# Embedded_Circuits.net
KiCad netlist of a schematic drawn in Altium Designer
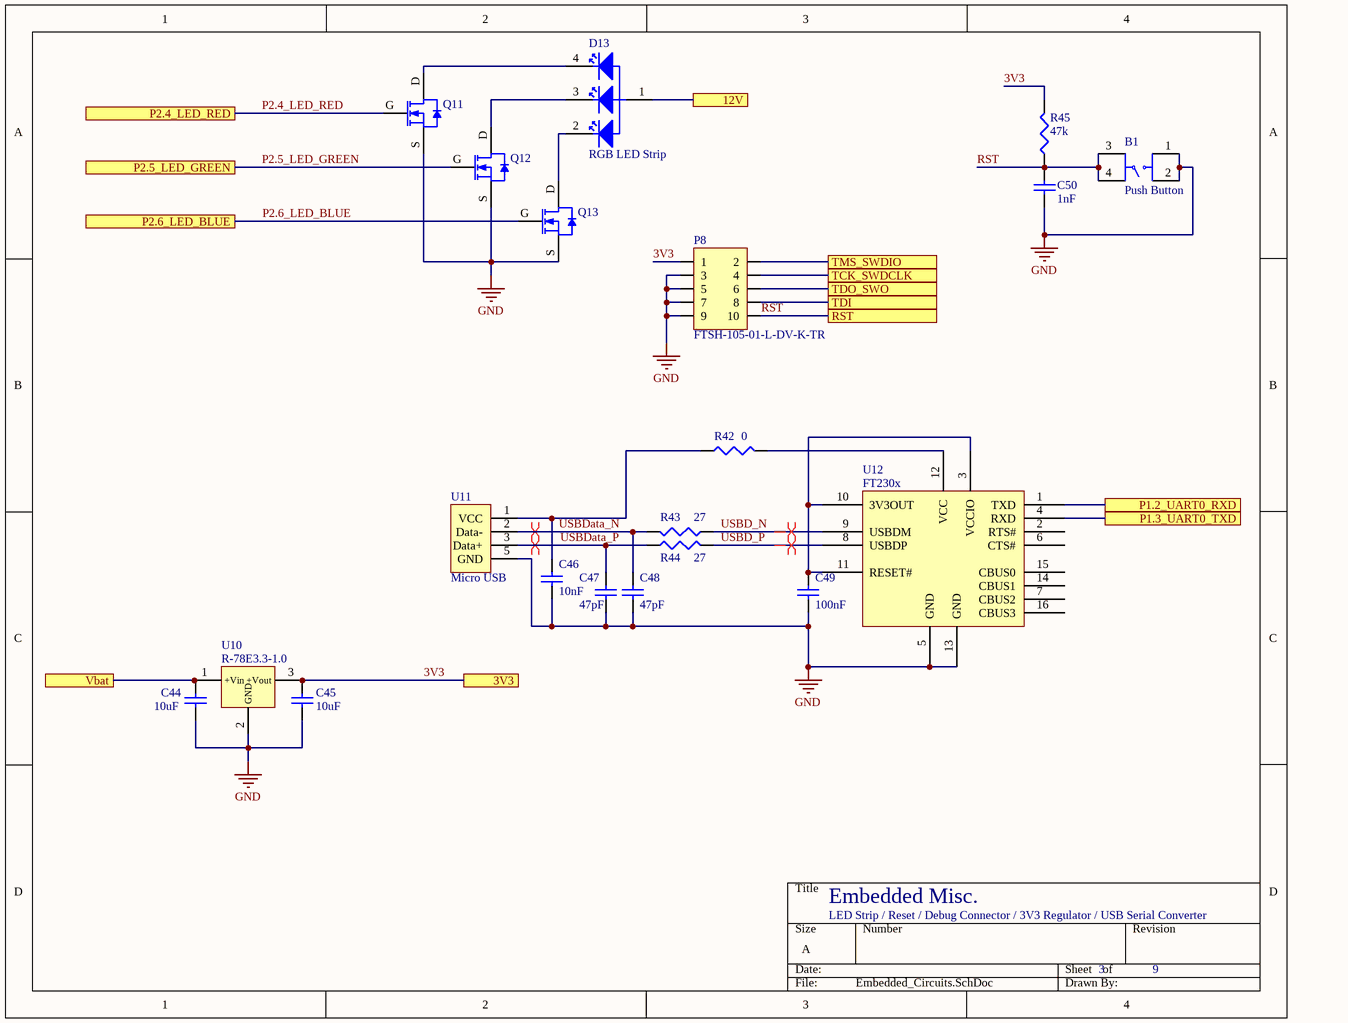
[diagram p0: Embedded_Circuits.SchDoc]

(export (version "E")
  (design (tool "Eeschema 10.0.6"))
  (components
    (comp (ref "B1")
      (value "Push Button")
      (footprint "Push Button")
      (description "Tactile Switch SPST-NO Top Actuated Through Hole")
      (libsource (lib "Power_Embedded_Board_Library") (part "Push Button"))
    )
    (comp (ref "C44")
      (value "10uF")
      (footprint "C1206")
      (description "Capacitor")
      (fields (field (name "Comment") "Cap") (field (name "PUBLISHER") "Altium Limited"))
      (libsource (lib "Miscellaneous Devices") (part "Cap"))
    )
    (comp (ref "C45")
      (value "10uF")
      (footprint "C1206")
      (description "Capacitor")
      (fields (field (name "Comment") "Cap") (field (name "PUBLISHER") "Altium Limited"))
      (libsource (lib "Miscellaneous Devices") (part "Cap"))
    )
    (comp (ref "C46")
      (value "10nF")
      (footprint "C1206")
      (description "Capacitor")
      (fields (field (name "Comment") "Cap") (field (name "PUBLISHER") "Altium Limited"))
      (libsource (lib "Miscellaneous Devices") (part "Cap"))
    )
    (comp (ref "C47")
      (value "47pF")
      (footprint "C1206")
      (description "Capacitor")
      (fields (field (name "Comment") "Cap") (field (name "PUBLISHER") "Altium Limited"))
      (libsource (lib "Miscellaneous Devices") (part "Cap"))
    )
    (comp (ref "C48")
      (value "47pF")
      (footprint "C1206")
      (description "Capacitor")
      (fields (field (name "Comment") "Cap") (field (name "PUBLISHER") "Altium Limited"))
      (libsource (lib "Miscellaneous Devices") (part "Cap"))
    )
    (comp (ref "C49")
      (value "100nF")
      (footprint "C1206")
      (description "Capacitor")
      (fields (field (name "Comment") "Cap") (field (name "PUBLISHER") "Altium Limited"))
      (libsource (lib "Miscellaneous Devices") (part "Cap"))
    )
    (comp (ref "C50")
      (value "1nF")
      (footprint "C1206")
      (description "Capacitor (Semiconductor SIM Model)")
      (fields (field (name "Comment") "Cap Semi") (field (name "PUBLISHER") "Altium Limited"))
      (libsource (lib "Miscellaneous Devices") (part "Cap Semi"))
    )
    (comp (ref "D13")
      (value "RGB LED Strip")
      (footprint "Header 1x4")
      (description "LED RGB Strip - Bare Nonaddressable")
      (libsource (lib "Power_Embedded_Board_Library") (part "RGB LED Strip"))
    )
    (comp (ref "P8")
      (value "FTSH-105-01-L-DV-K-TR")
      (footprint "FTSH-105-01-L-DV-K-TR")
      (description "CONN HEADER 10POS DUAL .05\" SMD")
      (libsource (lib "Power_Embedded_Board_Library") (part "JTAG Header"))
    )
    (comp (ref "Q11")
      (value "DMN1019USN")
      (footprint "DMN1019USN")
      (description "12V N-Channel Enhancement Mode MOSFET")
      (libsource (lib "Power_Embedded_Board_Library") (part "DMN1019USN"))
    )
    (comp (ref "Q12")
      (value "DMN1019USN")
      (footprint "DMN1019USN")
      (description "12V N-Channel Enhancement Mode MOSFET")
      (libsource (lib "Power_Embedded_Board_Library") (part "DMN1019USN"))
    )
    (comp (ref "Q13")
      (value "DMN1019USN")
      (footprint "DMN1019USN")
      (description "12V N-Channel Enhancement Mode MOSFET")
      (libsource (lib "Power_Embedded_Board_Library") (part "DMN1019USN"))
    )
    (comp (ref "R42")
      (value "0")
      (footprint "J1-0603")
      (description "Resistor")
      (fields (field (name "Comment") "Res3") (field (name "PUBLISHER") "Altium Limited"))
      (libsource (lib "Miscellaneous Devices") (part "Res3"))
    )
    (comp (ref "R43")
      (value "27")
      (footprint "J1-0603")
      (description "Resistor")
      (fields (field (name "Comment") "Res3") (field (name "PUBLISHER") "Altium Limited"))
      (libsource (lib "Miscellaneous Devices") (part "Res3"))
    )
    (comp (ref "R44")
      (value "27")
      (footprint "J1-0603")
      (description "Resistor")
      (fields (field (name "Comment") "Res3") (field (name "PUBLISHER") "Altium Limited"))
      (libsource (lib "Miscellaneous Devices") (part "Res3"))
    )
    (comp (ref "R45")
      (value "47k")
      (footprint "J1-0603")
      (description "Resistor")
      (fields (field (name "Comment") "Res3") (field (name "PUBLISHER") "Altium Limited"))
      (libsource (lib "Miscellaneous Devices") (part "Res3"))
    )
    (comp (ref "U10")
      (value "R-78E3.3-1.0")
      (footprint "R-78Exx-1.0")
      (description "1A DC/DC Voltage Converter")
      (libsource (lib "Power_Embedded_Board_Library") (part "R-78Exx-1.0"))
    )
    (comp (ref "U11")
      (value "Micro USB")
      (footprint "Micro USB")
      (description "USB - micro B USB 2.0 Receptacle Connector 5 Position Surface Mount, Right Angle")
      (libsource (lib "Power_Embedded_Board_Library") (part "Micro USB"))
    )
    (comp (ref "U12")
      (value "FT230x")
      (footprint "FT230X")
      (description "USB to Basic UART IC")
      (libsource (lib "Power_Embedded_Board_Library") (part "FTDI FT230x"))
    )
  )
  (nets
    (net (code "1") (name "/3V3") (class "Default")
      (node (ref "C45") (pin "2") (pinfunction "2_2") (pintype "passive"))
      (node (ref "P8") (pin "1") (pinfunction "1_1") (pintype "passive"))
      (node (ref "R45") (pin "2") (pinfunction "2_2") (pintype "passive"))
      (node (ref "U10") (pin "3") (pinfunction "+Vout_3") (pintype "passive"))
    )
    (net (code "2") (name "/12V") (class "Default")
      (node (ref "D13") (pin "1") (pinfunction "1_1") (pintype "passive"))
    )
    (net (code "3") (name "/P1.2_UART0_RXD") (class "Default")
      (node (ref "U12") (pin "1") (pinfunction "TXD_1") (pintype "passive"))
    )
    (net (code "4") (name "/P1.3_UART0_TXD") (class "Default")
      (node (ref "U12") (pin "4") (pinfunction "RXD_4") (pintype "passive"))
    )
    (net (code "5") (name "/P2.4_LED_RED") (class "Default")
      (node (ref "Q11") (pin "G") (pinfunction "G_G") (pintype "passive"))
    )
    (net (code "6") (name "/P2.5_LED_GREEN") (class "Default")
      (node (ref "Q12") (pin "G") (pinfunction "G_G") (pintype "passive"))
    )
    (net (code "7") (name "/P2.6_LED_BLUE") (class "Default")
      (node (ref "Q13") (pin "G") (pinfunction "G_G") (pintype "passive"))
    )
    (net (code "8") (name "/RST") (class "Default")
      (node (ref "B1") (pin "3") (pinfunction "3_3") (pintype "passive"))
      (node (ref "B1") (pin "4") (pinfunction "4_4") (pintype "passive"))
      (node (ref "C50") (pin "2") (pinfunction "2_2") (pintype "passive"))
      (node (ref "P8") (pin "10") (pinfunction "10_10") (pintype "passive"))
      (node (ref "R45") (pin "1") (pinfunction "1_1") (pintype "passive"))
    )
    (net (code "9") (name "/TCK_SWDCLK") (class "Default")
      (node (ref "P8") (pin "4") (pinfunction "4_4") (pintype "passive"))
    )
    (net (code "10") (name "/TDI") (class "Default")
      (node (ref "P8") (pin "8") (pinfunction "8_8") (pintype "passive"))
    )
    (net (code "11") (name "/TDO_SWO") (class "Default")
      (node (ref "P8") (pin "6") (pinfunction "6_6") (pintype "passive"))
    )
    (net (code "12") (name "/TMS_SWDIO") (class "Default")
      (node (ref "P8") (pin "2") (pinfunction "2_2") (pintype "passive"))
    )
    (net (code "13") (name "/USBD_N") (class "Default")
      (node (ref "R43") (pin "1") (pinfunction "1_1") (pintype "passive"))
      (node (ref "U12") (pin "9") (pinfunction "USBDM_9") (pintype "passive"))
    )
    (net (code "14") (name "/USBD_P") (class "Default")
      (node (ref "R44") (pin "2") (pinfunction "2_2") (pintype "passive"))
      (node (ref "U12") (pin "8") (pinfunction "USBDP_8") (pintype "passive"))
    )
    (net (code "15") (name "/USBData_N") (class "Default")
      (node (ref "C48") (pin "2") (pinfunction "2_2") (pintype "passive"))
      (node (ref "R43") (pin "2") (pinfunction "2_2") (pintype "passive"))
      (node (ref "U11") (pin "2") (pinfunction "Data-_2") (pintype "passive"))
    )
    (net (code "16") (name "/USBData_P") (class "Default")
      (node (ref "C47") (pin "2") (pinfunction "2_2") (pintype "passive"))
      (node (ref "R44") (pin "1") (pinfunction "1_1") (pintype "passive"))
      (node (ref "U11") (pin "3") (pinfunction "Data+_3") (pintype "passive"))
    )
    (net (code "17") (name "/Vbat") (class "Default")
      (node (ref "C44") (pin "2") (pinfunction "2_2") (pintype "passive"))
      (node (ref "U10") (pin "1") (pinfunction "+Vin_1") (pintype "passive"))
    )
    (net (code "18") (name "GND") (class "Default")
      (node (ref "B1") (pin "1") (pinfunction "1_1") (pintype "passive"))
      (node (ref "B1") (pin "2") (pinfunction "2_2") (pintype "passive"))
      (node (ref "C44") (pin "1") (pinfunction "1_1") (pintype "passive"))
      (node (ref "C45") (pin "1") (pinfunction "1_1") (pintype "passive"))
      (node (ref "C46") (pin "1") (pinfunction "1_1") (pintype "passive"))
      (node (ref "C47") (pin "1") (pinfunction "1_1") (pintype "passive"))
      (node (ref "C48") (pin "1") (pinfunction "1_1") (pintype "passive"))
      (node (ref "C49") (pin "1") (pinfunction "1_1") (pintype "passive"))
      (node (ref "C50") (pin "1") (pinfunction "1_1") (pintype "passive"))
      (node (ref "P8") (pin "3") (pinfunction "3_3") (pintype "passive"))
      (node (ref "P8") (pin "5") (pinfunction "5_5") (pintype "passive"))
      (node (ref "P8") (pin "7") (pinfunction "7_7") (pintype "passive"))
      (node (ref "P8") (pin "9") (pinfunction "9_9") (pintype "passive"))
      (node (ref "Q11") (pin "S") (pinfunction "S_S") (pintype "passive"))
      (node (ref "Q12") (pin "S") (pinfunction "S_S") (pintype "passive"))
      (node (ref "Q13") (pin "S") (pinfunction "S_S") (pintype "passive"))
      (node (ref "U10") (pin "2") (pinfunction "GND_2") (pintype "passive"))
      (node (ref "U11") (pin "5") (pinfunction "GND_5") (pintype "passive"))
      (node (ref "U12") (pin "13") (pinfunction "GND_13") (pintype "passive"))
      (node (ref "U12") (pin "5") (pinfunction "GND_5") (pintype "passive"))
    )
    (net (code "19") (name "Net-(D13-Pad2)") (class "Default")
      (node (ref "D13") (pin "2") (pinfunction "2_2") (pintype "passive"))
      (node (ref "Q13") (pin "D") (pinfunction "D_D") (pintype "passive"))
    )
    (net (code "20") (name "Net-(D13-Pad3)") (class "Default")
      (node (ref "D13") (pin "3") (pinfunction "3_3") (pintype "passive"))
      (node (ref "Q12") (pin "D") (pinfunction "D_D") (pintype "passive"))
    )
    (net (code "21") (name "Net-(D13-Pad4)") (class "Default")
      (node (ref "D13") (pin "4") (pinfunction "4_4") (pintype "passive"))
      (node (ref "Q11") (pin "D") (pinfunction "D_D") (pintype "passive"))
    )
    (net (code "22") (name "Net-(U11-VCC)") (class "Default")
      (node (ref "C46") (pin "2") (pinfunction "2_2") (pintype "passive"))
      (node (ref "R42") (pin "1") (pinfunction "1_1") (pintype "passive"))
      (node (ref "U11") (pin "1") (pinfunction "VCC_1") (pintype "passive"))
    )
    (net (code "23") (name "Net-(U12-3V3OUT)") (class "Default")
      (node (ref "C49") (pin "2") (pinfunction "2_2") (pintype "passive"))
      (node (ref "U12") (pin "10") (pinfunction "3V3OUT_10") (pintype "passive"))
      (node (ref "U12") (pin "11") (pinfunction "RESET#_11") (pintype "passive"))
      (node (ref "U12") (pin "3") (pinfunction "VCCIO_3") (pintype "passive"))
    )
    (net (code "24") (name "Net-(U12-VCC)") (class "Default")
      (node (ref "R42") (pin "2") (pinfunction "2_2") (pintype "passive"))
      (node (ref "U12") (pin "12") (pinfunction "VCC_12") (pintype "passive"))
    )
    (net (code "25") (name "unconnected-(U12-CBUS0-Pad15)") (class "Default")
      (node (ref "U12") (pin "15") (pinfunction "CBUS0_15") (pintype "passive"))
    )
    (net (code "26") (name "unconnected-(U12-CBUS1-Pad14)") (class "Default")
      (node (ref "U12") (pin "14") (pinfunction "CBUS1_14") (pintype "passive"))
    )
    (net (code "27") (name "unconnected-(U12-CBUS2-Pad7)") (class "Default")
      (node (ref "U12") (pin "7") (pinfunction "CBUS2_7") (pintype "passive"))
    )
    (net (code "28") (name "unconnected-(U12-CBUS3-Pad16)") (class "Default")
      (node (ref "U12") (pin "16") (pinfunction "CBUS3_16") (pintype "passive"))
    )
    (net (code "29") (name "unconnected-(U12-CTS#-Pad6)") (class "Default")
      (node (ref "U12") (pin "6") (pinfunction "CTS#_6") (pintype "passive"))
    )
    (net (code "30") (name "unconnected-(U12-RTS#-Pad2)") (class "Default")
      (node (ref "U12") (pin "2") (pinfunction "RTS#_2") (pintype "passive"))
    )
  )
)
